# IndoorStation_PCB_M2.net
KiCad netlist of a schematic drawn in EAGLE
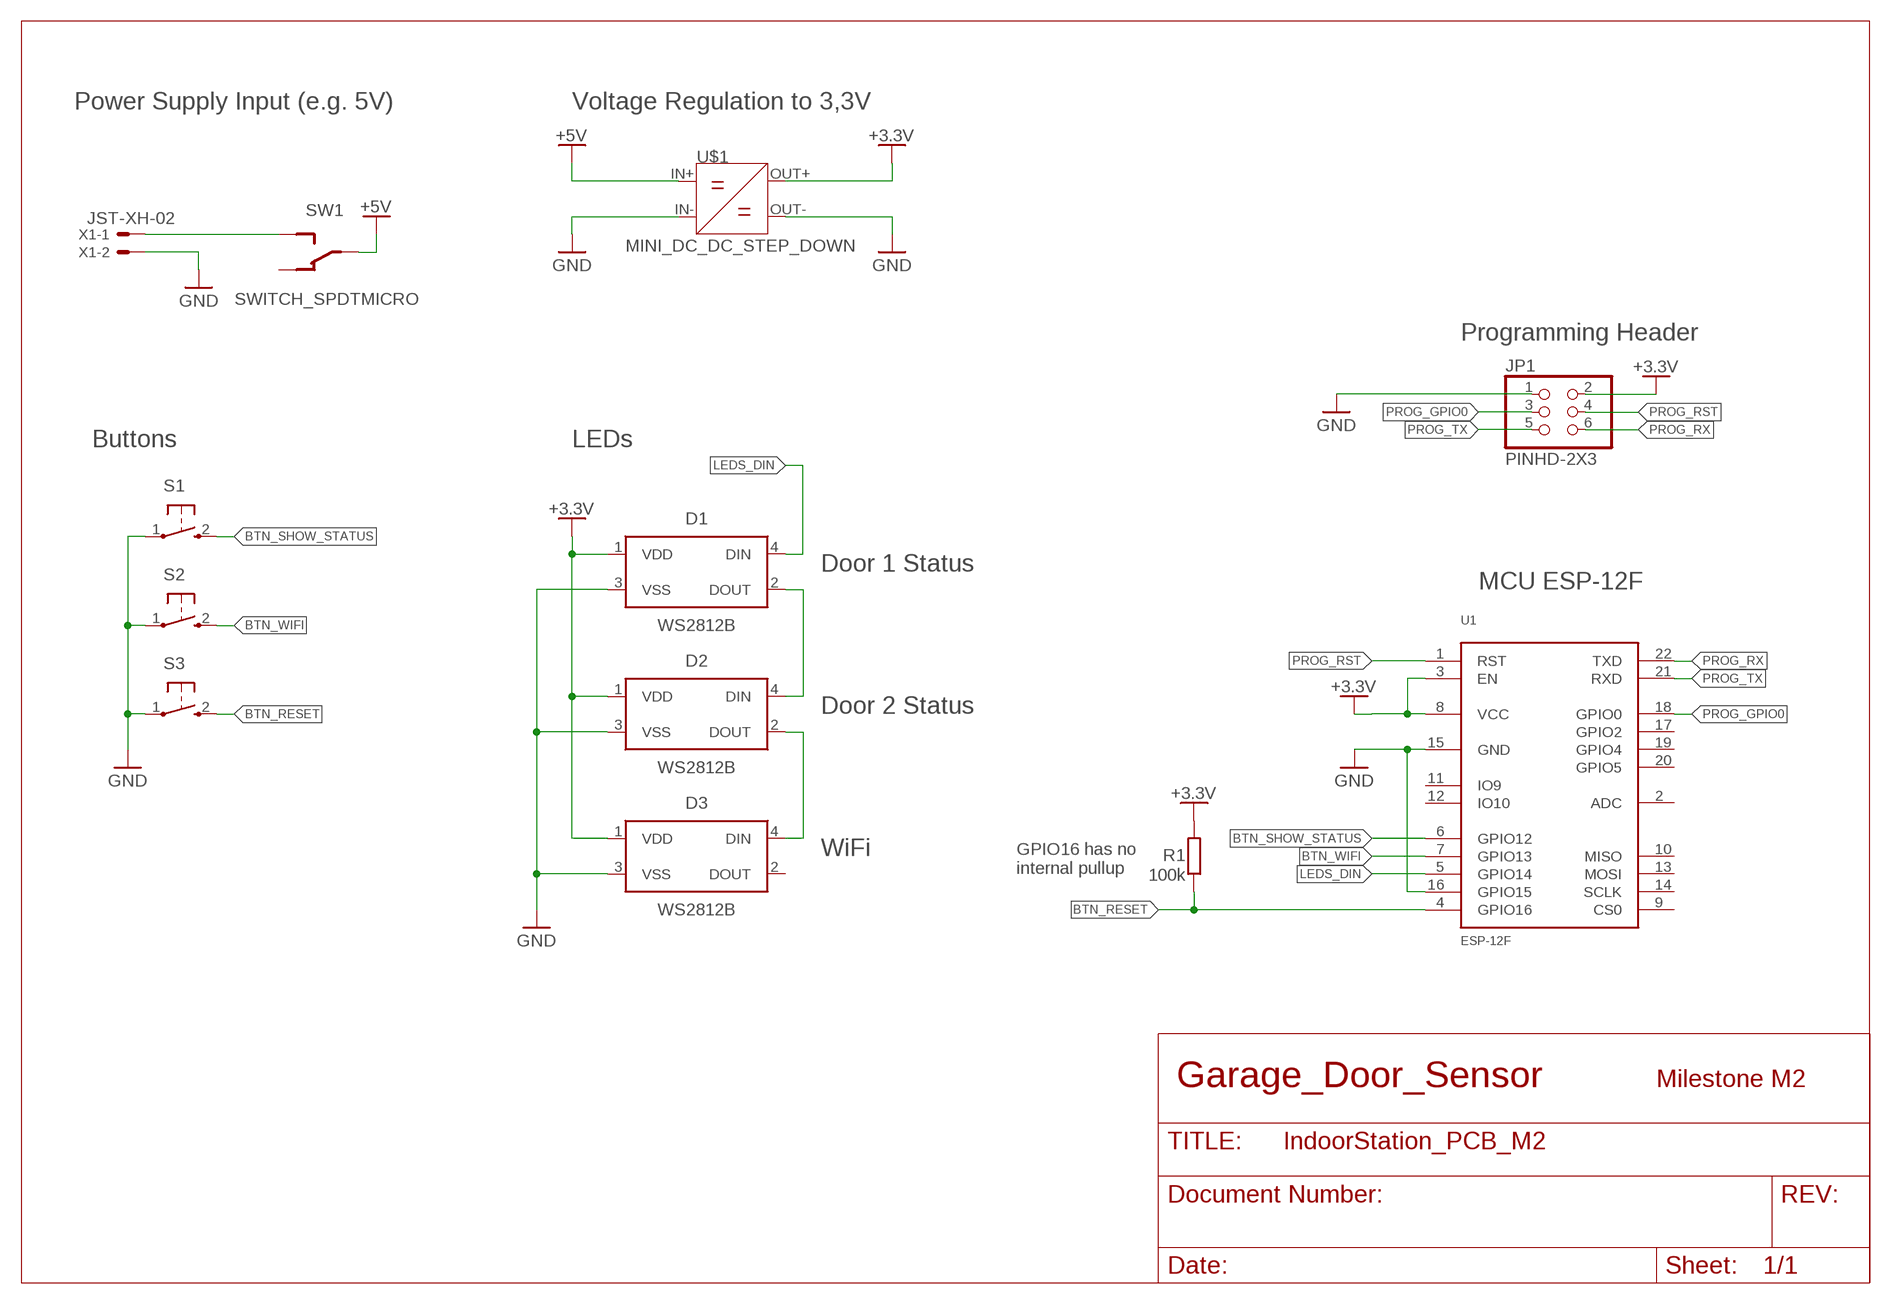
[diagram p0: schematic, sheet 1]

(export (version "E")
  (design (tool "Eeschema 10.0.6"))
  (components
    (comp (ref "D1")
      (value "WS2812B")
      (footprint "eagle-import:WS2812B")
      (fields (field (name "MANUFACTURER") "Worldsemi"))
      (libsource (lib "eagle-import") (part "WS2812B"))
    )
    (comp (ref "D2")
      (value "WS2812B")
      (footprint "eagle-import:WS2812B")
      (fields (field (name "MANUFACTURER") "Worldsemi"))
      (libsource (lib "eagle-import") (part "WS2812B"))
    )
    (comp (ref "D3")
      (value "WS2812B")
      (footprint "eagle-import:WS2812B")
      (fields (field (name "MANUFACTURER") "Worldsemi"))
      (libsource (lib "eagle-import") (part "WS2812B"))
    )
    (comp (ref "JP1")
      (value "PINHD-2X3")
      (footprint "eagle-import:2X03")
      (fields (field (name "MANUFACTURER") "Generic"))
      (libsource (lib "eagle-import") (part "PINHD-2X3"))
    )
    (comp (ref "R1")
      (value "100k")
      (footprint "eagle-import:R0805")
      (libsource (lib "eagle-import") (part "R-EU_R0805"))
    )
    (comp (ref "S1")
      (value "KURZHUBTASTER")
      (footprint "eagle-import:B3F-10XX")
      (libsource (lib "eagle-import") (part "KURZHUBTASTER"))
    )
    (comp (ref "S2")
      (value "KURZHUBTASTER")
      (footprint "eagle-import:B3F-10XX")
      (libsource (lib "eagle-import") (part "KURZHUBTASTER"))
    )
    (comp (ref "S3")
      (value "KURZHUBTASTER")
      (footprint "eagle-import:B3F-10XX")
      (libsource (lib "eagle-import") (part "KURZHUBTASTER"))
    )
    (comp (ref "SW1")
      (value "SWITCH_SPDTMICRO")
      (footprint "eagle-import:MICROSWITCH_SPDT")
      (libsource (lib "eagle-import") (part "SWITCH_SPDTMICRO"))
    )
    (comp (ref "U$1")
      (value "MINI_DC_DC_STEP_DOWN")
      (footprint "eagle-import:MINI_DC_DC_STEP_DOWN")
      (libsource (lib "eagle-import") (part "MINI_DC_DC_STEP_DOWN"))
    )
    (comp (ref "U1")
      (value "ESP-12F")
      (footprint "eagle-import:ESP-12F")
      (fields (field (name "MF") "AI-Thinker"))
      (libsource (lib "eagle-import") (part "ESP-12F"))
    )
    (comp (ref "X1")
      (value "JST-XH-02")
      (footprint "eagle-import:JST-XH-02-EDGE")
      (libsource (lib "eagle-import") (part "JST-XH-02-PIN-EDGE"))
    )
  )
  (nets
    (net (code "1") (name "+3.3V") (class "Default")
      (node (ref "D1") (pin "1") (pinfunction "VDD_1") (pintype "power_in"))
      (node (ref "D2") (pin "1") (pinfunction "VDD_1") (pintype "power_in"))
      (node (ref "D3") (pin "1") (pinfunction "VDD_1") (pintype "power_in"))
      (node (ref "JP1") (pin "2") (pinfunction "2_2") (pintype "passive"))
      (node (ref "R1") (pin "2") (pinfunction "2_2") (pintype "passive"))
      (node (ref "U$1") (pin "OUT+") (pinfunction "OUT+_OUT+") (pintype "output"))
      (node (ref "U1") (pin "3") (pinfunction "EN_3") (pintype "bidirectional"))
      (node (ref "U1") (pin "8") (pinfunction "VCC_8") (pintype "bidirectional"))
    )
    (net (code "2") (name "+5V") (class "Default")
      (node (ref "SW1") (pin "P$2") (pinfunction "P$2_P$2") (pintype "passive"))
      (node (ref "U$1") (pin "IN+") (pinfunction "IN+_IN+") (pintype "input"))
    )
    (net (code "3") (name "BTN_RESET") (class "Default")
      (node (ref "R1") (pin "1") (pinfunction "1_1") (pintype "passive"))
      (node (ref "S3") (pin "2") (pinfunction "S_2") (pintype "passive"))
      (node (ref "U1") (pin "4") (pinfunction "GPIO16_4") (pintype "bidirectional"))
    )
    (net (code "4") (name "BTN_SHOW_STATUS") (class "Default")
      (node (ref "S1") (pin "2") (pinfunction "S_2") (pintype "passive"))
      (node (ref "U1") (pin "6") (pinfunction "GPIO12_6") (pintype "bidirectional"))
    )
    (net (code "5") (name "BTN_WIFI") (class "Default")
      (node (ref "S2") (pin "2") (pinfunction "S_2") (pintype "passive"))
      (node (ref "U1") (pin "7") (pinfunction "GPIO13_7") (pintype "bidirectional"))
    )
    (net (code "6") (name "GND") (class "Default")
      (node (ref "D1") (pin "3") (pinfunction "VSS_3") (pintype "power_in"))
      (node (ref "D2") (pin "3") (pinfunction "VSS_3") (pintype "power_in"))
      (node (ref "D3") (pin "3") (pinfunction "VSS_3") (pintype "power_in"))
      (node (ref "JP1") (pin "1") (pinfunction "1_1") (pintype "passive"))
      (node (ref "S1") (pin "1") (pinfunction "P_1") (pintype "passive"))
      (node (ref "S2") (pin "1") (pinfunction "P_1") (pintype "passive"))
      (node (ref "S3") (pin "1") (pinfunction "P_1") (pintype "passive"))
      (node (ref "U$1") (pin "IN-") (pinfunction "IN-_IN-") (pintype "input"))
      (node (ref "U$1") (pin "OUT-") (pinfunction "OUT-_OUT-") (pintype "output"))
      (node (ref "U1") (pin "15") (pinfunction "GND_15") (pintype "bidirectional"))
      (node (ref "U1") (pin "16") (pinfunction "GPIO15_16") (pintype "bidirectional"))
      (node (ref "X1") (pin "P$2") (pinfunction "S_P$2") (pintype "passive"))
    )
    (net (code "7") (name "LEDS_DIN") (class "Default")
      (node (ref "D1") (pin "4") (pinfunction "DIN_4") (pintype "input"))
      (node (ref "U1") (pin "5") (pinfunction "GPIO14_5") (pintype "bidirectional"))
    )
    (net (code "8") (name "Net-(D1-DOUT)") (class "Default")
      (node (ref "D1") (pin "2") (pinfunction "DOUT_2") (pintype "output"))
      (node (ref "D2") (pin "4") (pinfunction "DIN_4") (pintype "input"))
    )
    (net (code "9") (name "Net-(D2-DOUT)") (class "Default")
      (node (ref "D2") (pin "2") (pinfunction "DOUT_2") (pintype "output"))
      (node (ref "D3") (pin "4") (pinfunction "DIN_4") (pintype "input"))
    )
    (net (code "10") (name "Net-(X1A-S)") (class "Default")
      (node (ref "SW1") (pin "P$1") (pinfunction "P$1_P$1") (pintype "passive"))
      (node (ref "X1") (pin "P$1") (pinfunction "S_P$1") (pintype "passive"))
    )
    (net (code "11") (name "PROG_GPIO0") (class "Default")
      (node (ref "JP1") (pin "3") (pinfunction "3_3") (pintype "passive"))
      (node (ref "U1") (pin "18") (pinfunction "GPIO0_18") (pintype "bidirectional"))
    )
    (net (code "12") (name "PROG_RST") (class "Default")
      (node (ref "JP1") (pin "4") (pinfunction "4_4") (pintype "passive"))
      (node (ref "U1") (pin "1") (pinfunction "RST_1") (pintype "bidirectional"))
    )
    (net (code "13") (name "PROG_RX") (class "Default")
      (node (ref "JP1") (pin "6") (pinfunction "6_6") (pintype "passive"))
      (node (ref "U1") (pin "22") (pinfunction "TXD_22") (pintype "bidirectional"))
    )
    (net (code "14") (name "PROG_TX") (class "Default")
      (node (ref "JP1") (pin "5") (pinfunction "5_5") (pintype "passive"))
      (node (ref "U1") (pin "21") (pinfunction "RXD_21") (pintype "bidirectional"))
    )
    (net (code "15") (name "unconnected-(D3-DOUT-Pad2)") (class "Default")
      (node (ref "D3") (pin "2") (pinfunction "DOUT_2") (pintype "output"))
    )
    (net (code "16") (name "unconnected-(SW1-PadP$3)") (class "Default")
      (node (ref "SW1") (pin "P$3") (pinfunction "P$3_P$3") (pintype "passive"))
    )
    (net (code "17") (name "unconnected-(U1-ADC-Pad2)") (class "Default")
      (node (ref "U1") (pin "2") (pinfunction "ADC_2") (pintype "bidirectional"))
    )
    (net (code "18") (name "unconnected-(U1-CS0-Pad9)") (class "Default")
      (node (ref "U1") (pin "9") (pinfunction "CS0_9") (pintype "bidirectional"))
    )
    (net (code "19") (name "unconnected-(U1-GPIO2-Pad17)") (class "Default")
      (node (ref "U1") (pin "17") (pinfunction "GPIO2_17") (pintype "bidirectional"))
    )
    (net (code "20") (name "unconnected-(U1-GPIO4-Pad19)") (class "Default")
      (node (ref "U1") (pin "19") (pinfunction "GPIO4_19") (pintype "bidirectional"))
    )
    (net (code "21") (name "unconnected-(U1-GPIO5-Pad20)") (class "Default")
      (node (ref "U1") (pin "20") (pinfunction "GPIO5_20") (pintype "bidirectional"))
    )
    (net (code "22") (name "unconnected-(U1-IO9-Pad11)") (class "Default")
      (node (ref "U1") (pin "11") (pinfunction "IO9_11") (pintype "bidirectional"))
    )
    (net (code "23") (name "unconnected-(U1-IO10-Pad12)") (class "Default")
      (node (ref "U1") (pin "12") (pinfunction "IO10_12") (pintype "bidirectional"))
    )
    (net (code "24") (name "unconnected-(U1-MISO-Pad10)") (class "Default")
      (node (ref "U1") (pin "10") (pinfunction "MISO_10") (pintype "bidirectional"))
    )
    (net (code "25") (name "unconnected-(U1-MOSI-Pad13)") (class "Default")
      (node (ref "U1") (pin "13") (pinfunction "MOSI_13") (pintype "bidirectional"))
    )
    (net (code "26") (name "unconnected-(U1-SCLK-Pad14)") (class "Default")
      (node (ref "U1") (pin "14") (pinfunction "SCLK_14") (pintype "bidirectional"))
    )
  )
)
